# 1_RKSTM32_Power.net
KiCad netlist of a schematic drawn in Altium Designer
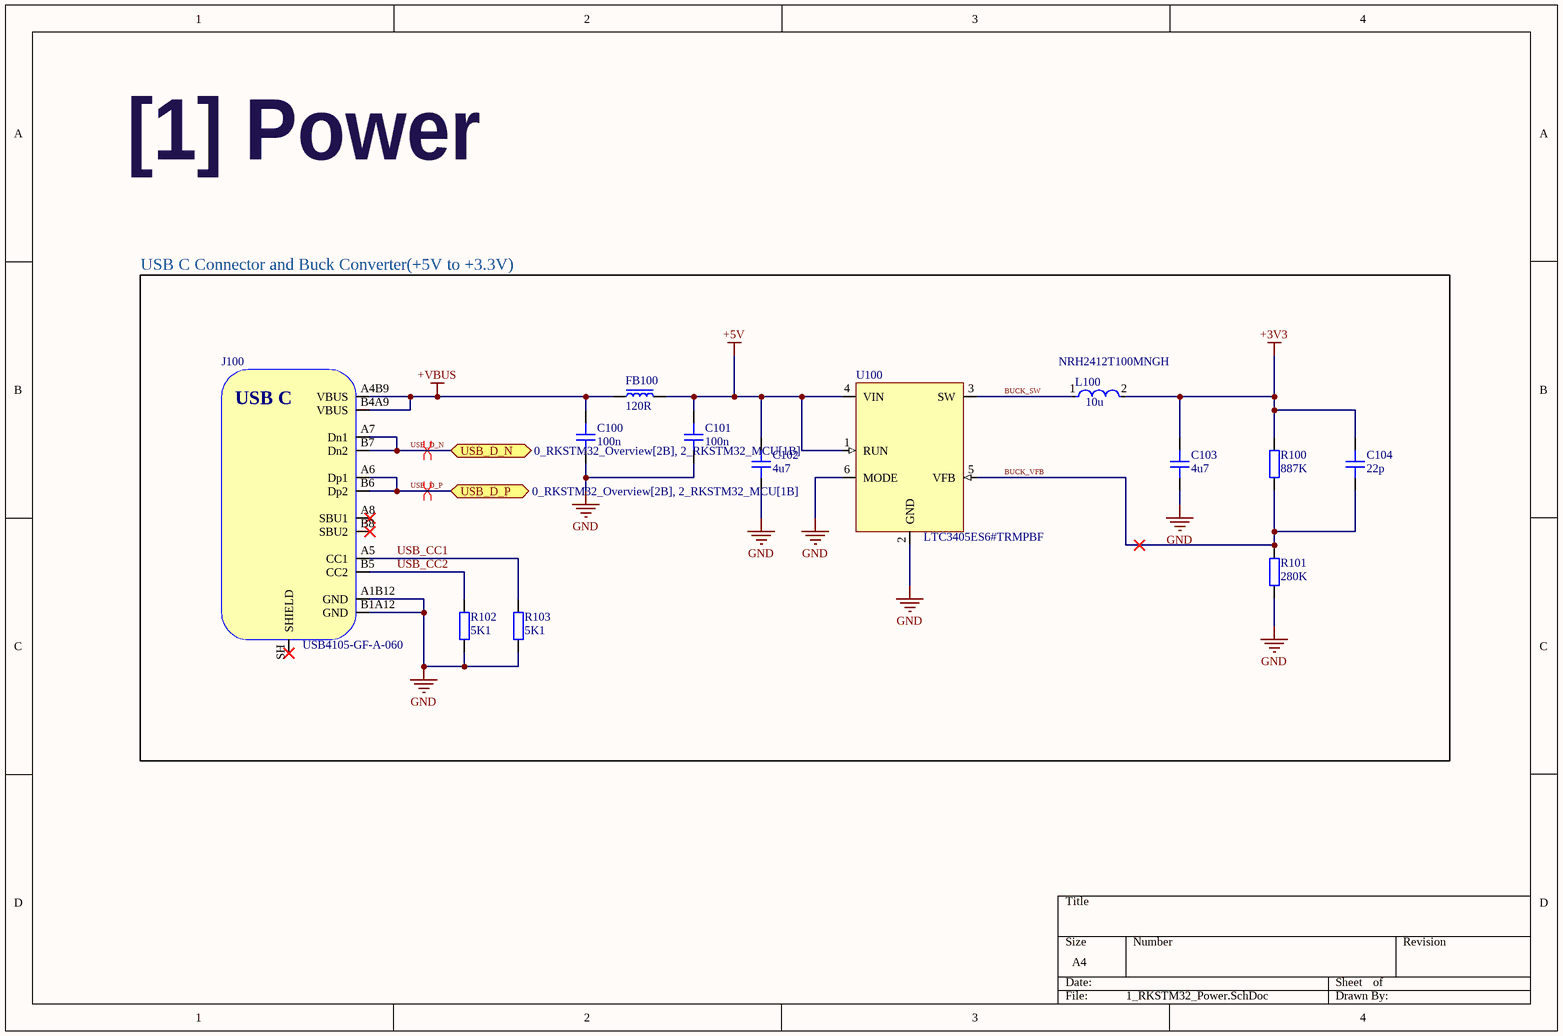
[diagram p0: 1_RKSTM32_Power.SchDoc]

(export (version "E")
  (design (tool "Eeschema 10.0.6"))
  (components
    (comp (ref "C100")
      (value "100n")
      (footprint "CAP_0805")
      (description "Capacitor SMD 0805")
      (libsource (lib "Schematic-Lib-PhilsLab") (part "CAP_0805"))
    )
    (comp (ref "C101")
      (value "100n")
      (footprint "CAP_0805")
      (description "Capacitor SMD 0805")
      (libsource (lib "Schematic-Lib-PhilsLab") (part "CAP_0805"))
    )
    (comp (ref "C102")
      (value "4u7")
      (footprint "CAP_0805")
      (description "Capacitor SMD 0805")
      (libsource (lib "Schematic-Lib-PhilsLab") (part "CAP_0805"))
    )
    (comp (ref "C103")
      (value "4u7")
      (footprint "CAP_0805")
      (description "Capacitor SMD 0805")
      (libsource (lib "Schematic-Lib-PhilsLab") (part "CAP_0805"))
    )
    (comp (ref "C104")
      (value "22p")
      (footprint "CAP_0603")
      (description "Capacitor SMD 0603")
      (libsource (lib "Schematic-Lib-PhilsLab") (part "CAP_0603"))
    )
    (comp (ref "FB100")
      (value "120R")
      (footprint "FB_0603")
      (description "Ferrite Bead SMD 0603")
      (libsource (lib "Schematic-Lib-PhilsLab") (part "FB_0603"))
    )
    (comp (ref "J100")
      (value "USB4105-GF-A-060")
      (footprint "USB4105-GF-A-060")
      (description "USB Connector Type C SMT 12 Pin")
      (fields (field (name "MANUFACTURER") "GCT"))
      (libsource (lib "Schematic-Lib-PhilsLab") (part "USB4105-GF-A-060"))
    )
    (comp (ref "L100")
      (value "10u")
      (footprint "FP-NRH2412-MFG")
      (description "Shielded Wirewound Inductor 10uH 20% 0.51A 0.72Ω SMD")
      (fields (field (name "TOLERANCE") "20%"))
      (libsource (lib "Altium Content Vault") (part "725321dda6339637d4d059423bc1c3c"))
    )
    (comp (ref "R100")
      (value "887K")
      (footprint "RES_0603")
      (description "Resistor SMD 0603")
      (libsource (lib "Schematic-Lib-PhilsLab") (part "RES_0603"))
    )
    (comp (ref "R101")
      (value "280K")
      (footprint "RES_0603")
      (description "Resistor SMD 0603")
      (libsource (lib "Schematic-Lib-PhilsLab") (part "RES_0603"))
    )
    (comp (ref "R102")
      (value "5K1")
      (footprint "RES_0603")
      (description "Resistor SMD 0603")
      (libsource (lib "Schematic-Lib-PhilsLab") (part "RES_0603"))
    )
    (comp (ref "R103")
      (value "5K1")
      (footprint "RES_0603")
      (description "Resistor SMD 0603")
      (libsource (lib "Schematic-Lib-PhilsLab") (part "RES_0603"))
    )
    (comp (ref "U100")
      (value "LTC3405ES6#TRMPBF")
      (footprint "SOT-23-6")
      (description "1.5MHz, 300mA\r\nSynchronous Step-Down\r\nRegulator in ThinSOT")
      (fields (field (name "MANUFACTURER") "Analog Devices"))
      (libsource (lib "Schematic-Lib-PhilsLab") (part "LTC3405ES6#TRMPBF"))
    )
  )
  (nets
    (net (code "1") (name "+3V3") (class "Default")
      (node (ref "C103") (pin "2") (pinfunction "2_2") (pintype "passive"))
      (node (ref "C104") (pin "2") (pinfunction "2_2") (pintype "passive"))
      (node (ref "L100") (pin "2") (pinfunction "2_2") (pintype "passive"))
      (node (ref "R100") (pin "2") (pinfunction "2_2") (pintype "passive"))
    )
    (net (code "2") (name "+5V") (class "Default")
      (node (ref "C101") (pin "2") (pinfunction "2_2") (pintype "passive"))
      (node (ref "C102") (pin "2") (pinfunction "2_2") (pintype "passive"))
      (node (ref "FB100") (pin "2") (pinfunction "2_2") (pintype "passive"))
      (node (ref "U100") (pin "1") (pinfunction "RUN_1") (pintype "input"))
      (node (ref "U100") (pin "4") (pinfunction "VIN_4") (pintype "power_in"))
    )
    (net (code "3") (name "+VBUS") (class "Default")
      (node (ref "C100") (pin "2") (pinfunction "2_2") (pintype "passive"))
      (node (ref "FB100") (pin "1") (pinfunction "1_1") (pintype "passive"))
      (node (ref "J100") (pin "A4B9") (pinfunction "VBUS_A4B9") (pintype "passive"))
      (node (ref "J100") (pin "B4A9") (pinfunction "VBUS_B4A9") (pintype "passive"))
    )
    (net (code "4") (name "/BUCK_SW") (class "Default")
      (node (ref "L100") (pin "1") (pinfunction "1_1") (pintype "passive"))
      (node (ref "U100") (pin "3") (pinfunction "SW_3") (pintype "power_in"))
    )
    (net (code "5") (name "/BUCK_VFB") (class "Default")
      (node (ref "C104") (pin "1") (pinfunction "1_1") (pintype "passive"))
      (node (ref "R100") (pin "1") (pinfunction "1_1") (pintype "passive"))
      (node (ref "R101") (pin "2") (pinfunction "2_2") (pintype "passive"))
      (node (ref "U100") (pin "5") (pinfunction "VFB_5") (pintype "input"))
    )
    (net (code "6") (name "/USB_CC1") (class "Default")
      (node (ref "J100") (pin "A5") (pinfunction "CC1_A5") (pintype "passive"))
      (node (ref "R103") (pin "2") (pinfunction "2_2") (pintype "passive"))
    )
    (net (code "7") (name "/USB_CC2") (class "Default")
      (node (ref "J100") (pin "B5") (pinfunction "CC2_B5") (pintype "passive"))
      (node (ref "R102") (pin "2") (pinfunction "2_2") (pintype "passive"))
    )
    (net (code "8") (name "/USB_D_N") (class "Default")
      (node (ref "J100") (pin "A7") (pinfunction "Dn1_A7") (pintype "passive"))
      (node (ref "J100") (pin "B7") (pinfunction "Dn2_B7") (pintype "passive"))
    )
    (net (code "9") (name "/USB_D_P") (class "Default")
      (node (ref "J100") (pin "A6") (pinfunction "Dp1_A6") (pintype "passive"))
      (node (ref "J100") (pin "B6") (pinfunction "Dp2_B6") (pintype "passive"))
    )
    (net (code "10") (name "GND") (class "Default")
      (node (ref "C100") (pin "1") (pinfunction "1_1") (pintype "passive"))
      (node (ref "C101") (pin "1") (pinfunction "1_1") (pintype "passive"))
      (node (ref "C102") (pin "1") (pinfunction "1_1") (pintype "passive"))
      (node (ref "C103") (pin "1") (pinfunction "1_1") (pintype "passive"))
      (node (ref "J100") (pin "A1B12") (pinfunction "GND_A1B12") (pintype "passive"))
      (node (ref "J100") (pin "B1A12") (pinfunction "GND_B1A12") (pintype "passive"))
      (node (ref "R101") (pin "1") (pinfunction "1_1") (pintype "passive"))
      (node (ref "R102") (pin "1") (pinfunction "1_1") (pintype "passive"))
      (node (ref "R103") (pin "1") (pinfunction "1_1") (pintype "passive"))
      (node (ref "U100") (pin "2") (pinfunction "GND_2") (pintype "power_in"))
      (node (ref "U100") (pin "6") (pinfunction "MODE_6") (pintype "passive"))
    )
    (net (code "11") (name "unconnected-(J100-SBU1-PadA8)") (class "Default")
      (node (ref "J100") (pin "A8") (pinfunction "SBU1_A8") (pintype "passive+no_connect"))
    )
    (net (code "12") (name "unconnected-(J100-SBU2-PadB8)") (class "Default")
      (node (ref "J100") (pin "B8") (pinfunction "SBU2_B8") (pintype "passive+no_connect"))
    )
    (net (code "13") (name "unconnected-(J100-SHIELD-PadSH)") (class "Default")
      (node (ref "J100") (pin "SH") (pinfunction "SHIELD_SH") (pintype "passive+no_connect"))
    )
  )
)
